# Sheet1.net
KiCad netlist of a schematic drawn in Altium Designer
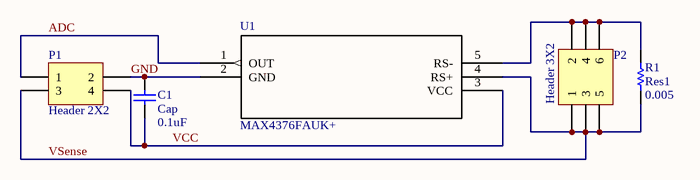
[diagram p0: Sheet1.SchDoc]

(export (version "E")
  (design (tool "Eeschema 10.0.6"))
  (components
    (comp (ref "C1")
      (value "Cap")
      (footprint "C0805")
      (description "Capacitor (Semiconductor SIM Model)")
      (fields (field (name "ALTIUM_VALUE") "0.1uF") (field (name "PUBLISHER") "Altium Limited"))
      (libsource (lib "Miscellaneous Devices") (part "Cap Semi"))
    )
    (comp (ref "P1")
      (value "Header 2X2")
      (footprint "HDR2X2")
      (description "Header, 2-Pin, Dual row")
      (fields (field (name "PUBLISHER") "Altium Limited"))
      (libsource (lib "Miscellaneous Connectors") (part "Header 2X2"))
    )
    (comp (ref "P2")
      (value "Header 3X2")
      (footprint "HDR2X3")
      (description "Header, 3-Pin, Dual row")
      (fields (field (name "PUBLISHER") "Altium Limited"))
      (libsource (lib "Miscellaneous Connectors") (part "Header 3X2"))
    )
    (comp (ref "R1")
      (value "Res1")
      (footprint "C1206")
      (description "Resistor")
      (fields (field (name "ALTIUM_VALUE") "0.005") (field (name "PUBLISHER") "Altium Limited"))
      (libsource (lib "Miscellaneous Devices") (part "Res1"))
    )
    (comp (ref "U1")
      (value "MAX4376FAUK+")
      (footprint "21-0057F")
      (description "Imported")
      (fields (field (name "MANUFACTURER_PART_NUMBER") "max4376fauk+"))
      (libsource (lib "Schlib") (part "MAX4376FAUK+"))
    )
  )
  (nets
    (net (code "1") (name "/ADC") (class "Default")
      (node (ref "P1") (pin "1") (pinfunction "1_1") (pintype "passive"))
      (node (ref "U1") (pin "1") (pinfunction "OUT_1") (pintype "output"))
    )
    (net (code "2") (name "/GND") (class "Default")
      (node (ref "C1") (pin "2") (pinfunction "2_2") (pintype "passive"))
      (node (ref "P1") (pin "2") (pinfunction "2_2") (pintype "passive"))
      (node (ref "U1") (pin "2") (pinfunction "GND_2") (pintype "power_in"))
    )
    (net (code "3") (name "/VCC") (class "Default")
      (node (ref "C1") (pin "1") (pinfunction "1_1") (pintype "passive"))
      (node (ref "P1") (pin "4") (pinfunction "4_4") (pintype "passive"))
      (node (ref "U1") (pin "3") (pinfunction "VCC_3") (pintype "power_in"))
    )
    (net (code "4") (name "/VSense") (class "Default")
      (node (ref "P1") (pin "3") (pinfunction "3_3") (pintype "passive"))
      (node (ref "P2") (pin "1") (pinfunction "1_1") (pintype "passive"))
      (node (ref "P2") (pin "3") (pinfunction "3_3") (pintype "passive"))
      (node (ref "P2") (pin "5") (pinfunction "5_5") (pintype "passive"))
      (node (ref "R1") (pin "1") (pinfunction "1_1") (pintype "passive"))
      (node (ref "U1") (pin "4") (pinfunction "RS+_4") (pintype "passive"))
    )
    (net (code "5") (name "Net-(U1-RS-)") (class "Default")
      (node (ref "P2") (pin "2") (pinfunction "2_2") (pintype "passive"))
      (node (ref "P2") (pin "4") (pinfunction "4_4") (pintype "passive"))
      (node (ref "P2") (pin "6") (pinfunction "6_6") (pintype "passive"))
      (node (ref "R1") (pin "2") (pinfunction "2_2") (pintype "passive"))
      (node (ref "U1") (pin "5") (pinfunction "RS-_5") (pintype "passive"))
    )
  )
)
